# stoplight.net
KiCad netlist of a schematic drawn in EAGLE
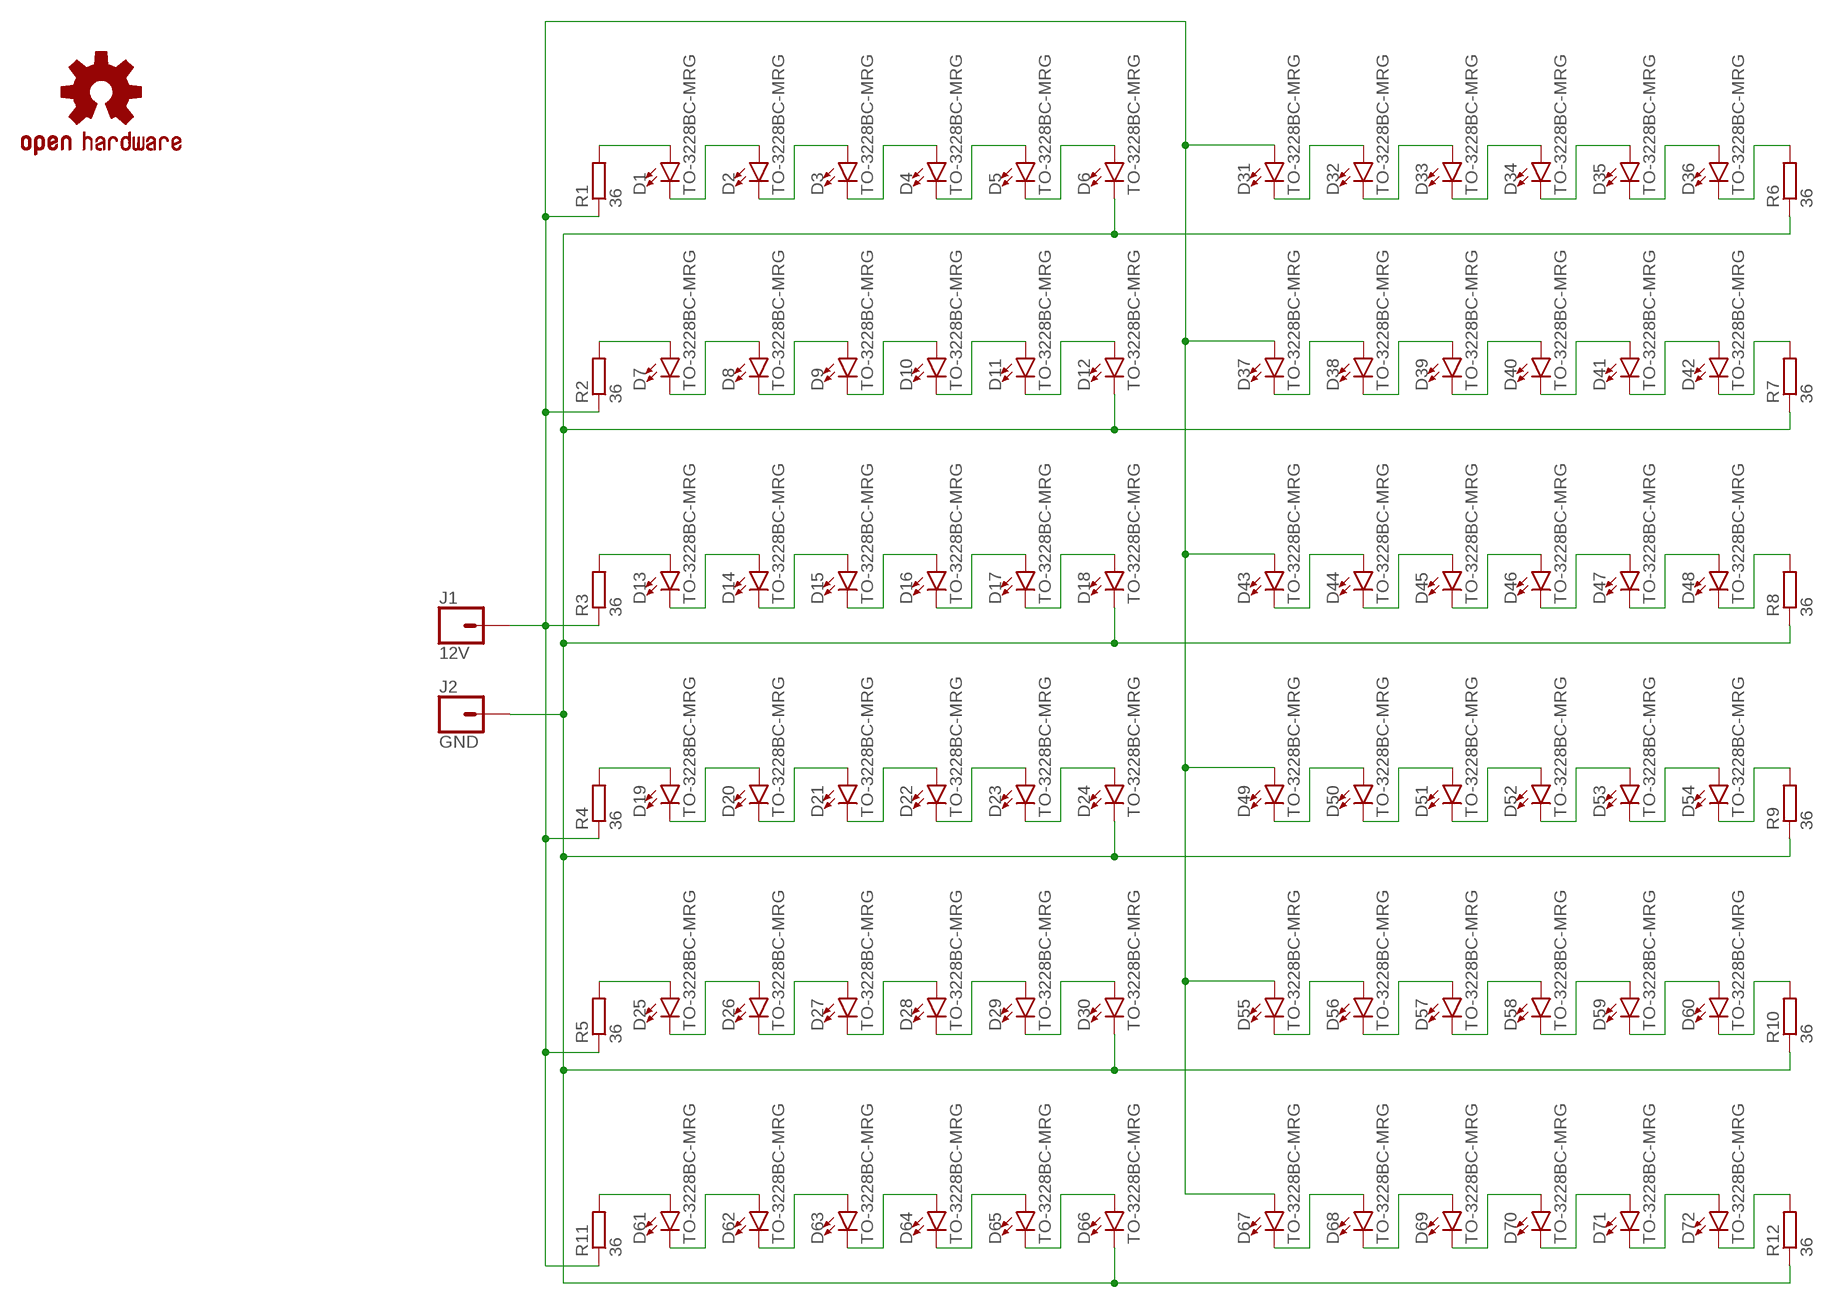
[diagram p0: schematic, sheet 1]

(export (version "E")
  (design (tool "Eeschema 10.0.6"))
  (components
    (comp (ref "D1")
      (value "TO-3228BC-MRG")
      (footprint "eagle-import:TO-3228BC")
      (libsource (lib "eagle-import") (part "TO-3228BC-MRG"))
    )
    (comp (ref "D2")
      (value "TO-3228BC-MRG")
      (footprint "eagle-import:TO-3228BC")
      (libsource (lib "eagle-import") (part "TO-3228BC-MRG"))
    )
    (comp (ref "D3")
      (value "TO-3228BC-MRG")
      (footprint "eagle-import:TO-3228BC")
      (libsource (lib "eagle-import") (part "TO-3228BC-MRG"))
    )
    (comp (ref "D4")
      (value "TO-3228BC-MRG")
      (footprint "eagle-import:TO-3228BC")
      (libsource (lib "eagle-import") (part "TO-3228BC-MRG"))
    )
    (comp (ref "D5")
      (value "TO-3228BC-MRG")
      (footprint "eagle-import:TO-3228BC")
      (libsource (lib "eagle-import") (part "TO-3228BC-MRG"))
    )
    (comp (ref "D6")
      (value "TO-3228BC-MRG")
      (footprint "eagle-import:TO-3228BC")
      (libsource (lib "eagle-import") (part "TO-3228BC-MRG"))
    )
    (comp (ref "D7")
      (value "TO-3228BC-MRG")
      (footprint "eagle-import:TO-3228BC")
      (libsource (lib "eagle-import") (part "TO-3228BC-MRG"))
    )
    (comp (ref "D8")
      (value "TO-3228BC-MRG")
      (footprint "eagle-import:TO-3228BC")
      (libsource (lib "eagle-import") (part "TO-3228BC-MRG"))
    )
    (comp (ref "D9")
      (value "TO-3228BC-MRG")
      (footprint "eagle-import:TO-3228BC")
      (libsource (lib "eagle-import") (part "TO-3228BC-MRG"))
    )
    (comp (ref "D10")
      (value "TO-3228BC-MRG")
      (footprint "eagle-import:TO-3228BC")
      (libsource (lib "eagle-import") (part "TO-3228BC-MRG"))
    )
    (comp (ref "D11")
      (value "TO-3228BC-MRG")
      (footprint "eagle-import:TO-3228BC")
      (libsource (lib "eagle-import") (part "TO-3228BC-MRG"))
    )
    (comp (ref "D12")
      (value "TO-3228BC-MRG")
      (footprint "eagle-import:TO-3228BC")
      (libsource (lib "eagle-import") (part "TO-3228BC-MRG"))
    )
    (comp (ref "D13")
      (value "TO-3228BC-MRG")
      (footprint "eagle-import:TO-3228BC")
      (libsource (lib "eagle-import") (part "TO-3228BC-MRG"))
    )
    (comp (ref "D14")
      (value "TO-3228BC-MRG")
      (footprint "eagle-import:TO-3228BC")
      (libsource (lib "eagle-import") (part "TO-3228BC-MRG"))
    )
    (comp (ref "D15")
      (value "TO-3228BC-MRG")
      (footprint "eagle-import:TO-3228BC")
      (libsource (lib "eagle-import") (part "TO-3228BC-MRG"))
    )
    (comp (ref "D16")
      (value "TO-3228BC-MRG")
      (footprint "eagle-import:TO-3228BC")
      (libsource (lib "eagle-import") (part "TO-3228BC-MRG"))
    )
    (comp (ref "D17")
      (value "TO-3228BC-MRG")
      (footprint "eagle-import:TO-3228BC")
      (libsource (lib "eagle-import") (part "TO-3228BC-MRG"))
    )
    (comp (ref "D18")
      (value "TO-3228BC-MRG")
      (footprint "eagle-import:TO-3228BC")
      (libsource (lib "eagle-import") (part "TO-3228BC-MRG"))
    )
    (comp (ref "D19")
      (value "TO-3228BC-MRG")
      (footprint "eagle-import:TO-3228BC")
      (libsource (lib "eagle-import") (part "TO-3228BC-MRG"))
    )
    (comp (ref "D20")
      (value "TO-3228BC-MRG")
      (footprint "eagle-import:TO-3228BC")
      (libsource (lib "eagle-import") (part "TO-3228BC-MRG"))
    )
    (comp (ref "D21")
      (value "TO-3228BC-MRG")
      (footprint "eagle-import:TO-3228BC")
      (libsource (lib "eagle-import") (part "TO-3228BC-MRG"))
    )
    (comp (ref "D22")
      (value "TO-3228BC-MRG")
      (footprint "eagle-import:TO-3228BC")
      (libsource (lib "eagle-import") (part "TO-3228BC-MRG"))
    )
    (comp (ref "D23")
      (value "TO-3228BC-MRG")
      (footprint "eagle-import:TO-3228BC")
      (libsource (lib "eagle-import") (part "TO-3228BC-MRG"))
    )
    (comp (ref "D24")
      (value "TO-3228BC-MRG")
      (footprint "eagle-import:TO-3228BC")
      (libsource (lib "eagle-import") (part "TO-3228BC-MRG"))
    )
    (comp (ref "D25")
      (value "TO-3228BC-MRG")
      (footprint "eagle-import:TO-3228BC")
      (libsource (lib "eagle-import") (part "TO-3228BC-MRG"))
    )
    (comp (ref "D26")
      (value "TO-3228BC-MRG")
      (footprint "eagle-import:TO-3228BC")
      (libsource (lib "eagle-import") (part "TO-3228BC-MRG"))
    )
    (comp (ref "D27")
      (value "TO-3228BC-MRG")
      (footprint "eagle-import:TO-3228BC")
      (libsource (lib "eagle-import") (part "TO-3228BC-MRG"))
    )
    (comp (ref "D28")
      (value "TO-3228BC-MRG")
      (footprint "eagle-import:TO-3228BC")
      (libsource (lib "eagle-import") (part "TO-3228BC-MRG"))
    )
    (comp (ref "D29")
      (value "TO-3228BC-MRG")
      (footprint "eagle-import:TO-3228BC")
      (libsource (lib "eagle-import") (part "TO-3228BC-MRG"))
    )
    (comp (ref "D30")
      (value "TO-3228BC-MRG")
      (footprint "eagle-import:TO-3228BC")
      (libsource (lib "eagle-import") (part "TO-3228BC-MRG"))
    )
    (comp (ref "D31")
      (value "TO-3228BC-MRG")
      (footprint "eagle-import:TO-3228BC")
      (libsource (lib "eagle-import") (part "TO-3228BC-MRG"))
    )
    (comp (ref "D32")
      (value "TO-3228BC-MRG")
      (footprint "eagle-import:TO-3228BC")
      (libsource (lib "eagle-import") (part "TO-3228BC-MRG"))
    )
    (comp (ref "D33")
      (value "TO-3228BC-MRG")
      (footprint "eagle-import:TO-3228BC")
      (libsource (lib "eagle-import") (part "TO-3228BC-MRG"))
    )
    (comp (ref "D34")
      (value "TO-3228BC-MRG")
      (footprint "eagle-import:TO-3228BC")
      (libsource (lib "eagle-import") (part "TO-3228BC-MRG"))
    )
    (comp (ref "D35")
      (value "TO-3228BC-MRG")
      (footprint "eagle-import:TO-3228BC")
      (libsource (lib "eagle-import") (part "TO-3228BC-MRG"))
    )
    (comp (ref "D36")
      (value "TO-3228BC-MRG")
      (footprint "eagle-import:TO-3228BC")
      (libsource (lib "eagle-import") (part "TO-3228BC-MRG"))
    )
    (comp (ref "D37")
      (value "TO-3228BC-MRG")
      (footprint "eagle-import:TO-3228BC")
      (libsource (lib "eagle-import") (part "TO-3228BC-MRG"))
    )
    (comp (ref "D38")
      (value "TO-3228BC-MRG")
      (footprint "eagle-import:TO-3228BC")
      (libsource (lib "eagle-import") (part "TO-3228BC-MRG"))
    )
    (comp (ref "D39")
      (value "TO-3228BC-MRG")
      (footprint "eagle-import:TO-3228BC")
      (libsource (lib "eagle-import") (part "TO-3228BC-MRG"))
    )
    (comp (ref "D40")
      (value "TO-3228BC-MRG")
      (footprint "eagle-import:TO-3228BC")
      (libsource (lib "eagle-import") (part "TO-3228BC-MRG"))
    )
    (comp (ref "D41")
      (value "TO-3228BC-MRG")
      (footprint "eagle-import:TO-3228BC")
      (libsource (lib "eagle-import") (part "TO-3228BC-MRG"))
    )
    (comp (ref "D42")
      (value "TO-3228BC-MRG")
      (footprint "eagle-import:TO-3228BC")
      (libsource (lib "eagle-import") (part "TO-3228BC-MRG"))
    )
    (comp (ref "D43")
      (value "TO-3228BC-MRG")
      (footprint "eagle-import:TO-3228BC")
      (libsource (lib "eagle-import") (part "TO-3228BC-MRG"))
    )
    (comp (ref "D44")
      (value "TO-3228BC-MRG")
      (footprint "eagle-import:TO-3228BC")
      (libsource (lib "eagle-import") (part "TO-3228BC-MRG"))
    )
    (comp (ref "D45")
      (value "TO-3228BC-MRG")
      (footprint "eagle-import:TO-3228BC")
      (libsource (lib "eagle-import") (part "TO-3228BC-MRG"))
    )
    (comp (ref "D46")
      (value "TO-3228BC-MRG")
      (footprint "eagle-import:TO-3228BC")
      (libsource (lib "eagle-import") (part "TO-3228BC-MRG"))
    )
    (comp (ref "D47")
      (value "TO-3228BC-MRG")
      (footprint "eagle-import:TO-3228BC")
      (libsource (lib "eagle-import") (part "TO-3228BC-MRG"))
    )
    (comp (ref "D48")
      (value "TO-3228BC-MRG")
      (footprint "eagle-import:TO-3228BC")
      (libsource (lib "eagle-import") (part "TO-3228BC-MRG"))
    )
    (comp (ref "D49")
      (value "TO-3228BC-MRG")
      (footprint "eagle-import:TO-3228BC")
      (libsource (lib "eagle-import") (part "TO-3228BC-MRG"))
    )
    (comp (ref "D50")
      (value "TO-3228BC-MRG")
      (footprint "eagle-import:TO-3228BC")
      (libsource (lib "eagle-import") (part "TO-3228BC-MRG"))
    )
    (comp (ref "D51")
      (value "TO-3228BC-MRG")
      (footprint "eagle-import:TO-3228BC")
      (libsource (lib "eagle-import") (part "TO-3228BC-MRG"))
    )
    (comp (ref "D52")
      (value "TO-3228BC-MRG")
      (footprint "eagle-import:TO-3228BC")
      (libsource (lib "eagle-import") (part "TO-3228BC-MRG"))
    )
    (comp (ref "D53")
      (value "TO-3228BC-MRG")
      (footprint "eagle-import:TO-3228BC")
      (libsource (lib "eagle-import") (part "TO-3228BC-MRG"))
    )
    (comp (ref "D54")
      (value "TO-3228BC-MRG")
      (footprint "eagle-import:TO-3228BC")
      (libsource (lib "eagle-import") (part "TO-3228BC-MRG"))
    )
    (comp (ref "D55")
      (value "TO-3228BC-MRG")
      (footprint "eagle-import:TO-3228BC")
      (libsource (lib "eagle-import") (part "TO-3228BC-MRG"))
    )
    (comp (ref "D56")
      (value "TO-3228BC-MRG")
      (footprint "eagle-import:TO-3228BC")
      (libsource (lib "eagle-import") (part "TO-3228BC-MRG"))
    )
    (comp (ref "D57")
      (value "TO-3228BC-MRG")
      (footprint "eagle-import:TO-3228BC")
      (libsource (lib "eagle-import") (part "TO-3228BC-MRG"))
    )
    (comp (ref "D58")
      (value "TO-3228BC-MRG")
      (footprint "eagle-import:TO-3228BC")
      (libsource (lib "eagle-import") (part "TO-3228BC-MRG"))
    )
    (comp (ref "D59")
      (value "TO-3228BC-MRG")
      (footprint "eagle-import:TO-3228BC")
      (libsource (lib "eagle-import") (part "TO-3228BC-MRG"))
    )
    (comp (ref "D60")
      (value "TO-3228BC-MRG")
      (footprint "eagle-import:TO-3228BC")
      (libsource (lib "eagle-import") (part "TO-3228BC-MRG"))
    )
    (comp (ref "D61")
      (value "TO-3228BC-MRG")
      (footprint "eagle-import:TO-3228BC")
      (libsource (lib "eagle-import") (part "TO-3228BC-MRG"))
    )
    (comp (ref "D62")
      (value "TO-3228BC-MRG")
      (footprint "eagle-import:TO-3228BC")
      (libsource (lib "eagle-import") (part "TO-3228BC-MRG"))
    )
    (comp (ref "D63")
      (value "TO-3228BC-MRG")
      (footprint "eagle-import:TO-3228BC")
      (libsource (lib "eagle-import") (part "TO-3228BC-MRG"))
    )
    (comp (ref "D64")
      (value "TO-3228BC-MRG")
      (footprint "eagle-import:TO-3228BC")
      (libsource (lib "eagle-import") (part "TO-3228BC-MRG"))
    )
    (comp (ref "D65")
      (value "TO-3228BC-MRG")
      (footprint "eagle-import:TO-3228BC")
      (libsource (lib "eagle-import") (part "TO-3228BC-MRG"))
    )
    (comp (ref "D66")
      (value "TO-3228BC-MRG")
      (footprint "eagle-import:TO-3228BC")
      (libsource (lib "eagle-import") (part "TO-3228BC-MRG"))
    )
    (comp (ref "D67")
      (value "TO-3228BC-MRG")
      (footprint "eagle-import:TO-3228BC")
      (libsource (lib "eagle-import") (part "TO-3228BC-MRG"))
    )
    (comp (ref "D68")
      (value "TO-3228BC-MRG")
      (footprint "eagle-import:TO-3228BC")
      (libsource (lib "eagle-import") (part "TO-3228BC-MRG"))
    )
    (comp (ref "D69")
      (value "TO-3228BC-MRG")
      (footprint "eagle-import:TO-3228BC")
      (libsource (lib "eagle-import") (part "TO-3228BC-MRG"))
    )
    (comp (ref "D70")
      (value "TO-3228BC-MRG")
      (footprint "eagle-import:TO-3228BC")
      (libsource (lib "eagle-import") (part "TO-3228BC-MRG"))
    )
    (comp (ref "D71")
      (value "TO-3228BC-MRG")
      (footprint "eagle-import:TO-3228BC")
      (libsource (lib "eagle-import") (part "TO-3228BC-MRG"))
    )
    (comp (ref "D72")
      (value "TO-3228BC-MRG")
      (footprint "eagle-import:TO-3228BC")
      (libsource (lib "eagle-import") (part "TO-3228BC-MRG"))
    )
    (comp (ref "J1")
      (value "12V")
      (footprint "eagle-import:1X01_LONGPAD")
      (libsource (lib "eagle-import") (part "CONN_01PTH_LONGPAD"))
    )
    (comp (ref "J2")
      (value "GND")
      (footprint "eagle-import:1X01_LONGPAD")
      (libsource (lib "eagle-import") (part "CONN_01PTH_LONGPAD"))
    )
    (comp (ref "LOGO1")
      (value "OSHW-LOGOS-COPPER")
      (footprint "eagle-import:OSHW-LOGO-S_COPPER")
      (libsource (lib "eagle-import") (part "OSHW-LOGOS-COPPER"))
    )
    (comp (ref "R1")
      (value "36")
      (footprint "eagle-import:R0805")
      (libsource (lib "eagle-import") (part "R-EU_R0805"))
    )
    (comp (ref "R2")
      (value "36")
      (footprint "eagle-import:R0805")
      (libsource (lib "eagle-import") (part "R-EU_R0805"))
    )
    (comp (ref "R3")
      (value "36")
      (footprint "eagle-import:R0805")
      (libsource (lib "eagle-import") (part "R-EU_R0805"))
    )
    (comp (ref "R4")
      (value "36")
      (footprint "eagle-import:R0805")
      (libsource (lib "eagle-import") (part "R-EU_R0805"))
    )
    (comp (ref "R5")
      (value "36")
      (footprint "eagle-import:R0805")
      (libsource (lib "eagle-import") (part "R-EU_R0805"))
    )
    (comp (ref "R6")
      (value "36")
      (footprint "eagle-import:R0805")
      (libsource (lib "eagle-import") (part "R-EU_R0805"))
    )
    (comp (ref "R7")
      (value "36")
      (footprint "eagle-import:R0805")
      (libsource (lib "eagle-import") (part "R-EU_R0805"))
    )
    (comp (ref "R8")
      (value "36")
      (footprint "eagle-import:R0805")
      (libsource (lib "eagle-import") (part "R-EU_R0805"))
    )
    (comp (ref "R9")
      (value "36")
      (footprint "eagle-import:R0805")
      (libsource (lib "eagle-import") (part "R-EU_R0805"))
    )
    (comp (ref "R10")
      (value "36")
      (footprint "eagle-import:R0805")
      (libsource (lib "eagle-import") (part "R-EU_R0805"))
    )
    (comp (ref "R11")
      (value "36")
      (footprint "eagle-import:R0805")
      (libsource (lib "eagle-import") (part "R-EU_R0805"))
    )
    (comp (ref "R12")
      (value "36")
      (footprint "eagle-import:R0805")
      (libsource (lib "eagle-import") (part "R-EU_R0805"))
    )
  )
  (nets
    (net (code "1") (name "Net-(D1-PadA)") (class "Default")
      (node (ref "D1") (pin "A") (pinfunction "A_A") (pintype "passive"))
      (node (ref "R1") (pin "2") (pinfunction "2_2") (pintype "passive"))
    )
    (net (code "2") (name "Net-(D1-PadC)") (class "Default")
      (node (ref "D1") (pin "C") (pinfunction "C_C") (pintype "passive"))
      (node (ref "D2") (pin "A") (pinfunction "A_A") (pintype "passive"))
    )
    (net (code "3") (name "Net-(D2-PadC)") (class "Default")
      (node (ref "D2") (pin "C") (pinfunction "C_C") (pintype "passive"))
      (node (ref "D3") (pin "A") (pinfunction "A_A") (pintype "passive"))
    )
    (net (code "4") (name "Net-(D3-PadC)") (class "Default")
      (node (ref "D3") (pin "C") (pinfunction "C_C") (pintype "passive"))
      (node (ref "D4") (pin "A") (pinfunction "A_A") (pintype "passive"))
    )
    (net (code "5") (name "Net-(D4-PadC)") (class "Default")
      (node (ref "D4") (pin "C") (pinfunction "C_C") (pintype "passive"))
      (node (ref "D5") (pin "A") (pinfunction "A_A") (pintype "passive"))
    )
    (net (code "6") (name "Net-(D5-PadC)") (class "Default")
      (node (ref "D5") (pin "C") (pinfunction "C_C") (pintype "passive"))
      (node (ref "D6") (pin "A") (pinfunction "A_A") (pintype "passive"))
    )
    (net (code "7") (name "Net-(D7-PadA)") (class "Default")
      (node (ref "D7") (pin "A") (pinfunction "A_A") (pintype "passive"))
      (node (ref "R2") (pin "2") (pinfunction "2_2") (pintype "passive"))
    )
    (net (code "8") (name "Net-(D7-PadC)") (class "Default")
      (node (ref "D7") (pin "C") (pinfunction "C_C") (pintype "passive"))
      (node (ref "D8") (pin "A") (pinfunction "A_A") (pintype "passive"))
    )
    (net (code "9") (name "Net-(D8-PadC)") (class "Default")
      (node (ref "D8") (pin "C") (pinfunction "C_C") (pintype "passive"))
      (node (ref "D9") (pin "A") (pinfunction "A_A") (pintype "passive"))
    )
    (net (code "10") (name "Net-(D10-PadA)") (class "Default")
      (node (ref "D10") (pin "A") (pinfunction "A_A") (pintype "passive"))
      (node (ref "D9") (pin "C") (pinfunction "C_C") (pintype "passive"))
    )
    (net (code "11") (name "Net-(D10-PadC)") (class "Default")
      (node (ref "D10") (pin "C") (pinfunction "C_C") (pintype "passive"))
      (node (ref "D11") (pin "A") (pinfunction "A_A") (pintype "passive"))
    )
    (net (code "12") (name "Net-(D11-PadC)") (class "Default")
      (node (ref "D11") (pin "C") (pinfunction "C_C") (pintype "passive"))
      (node (ref "D12") (pin "A") (pinfunction "A_A") (pintype "passive"))
    )
    (net (code "13") (name "Net-(D12-PadC)") (class "Default")
      (node (ref "D12") (pin "C") (pinfunction "C_C") (pintype "passive"))
      (node (ref "D18") (pin "C") (pinfunction "C_C") (pintype "passive"))
      (node (ref "D24") (pin "C") (pinfunction "C_C") (pintype "passive"))
      (node (ref "D30") (pin "C") (pinfunction "C_C") (pintype "passive"))
      (node (ref "D6") (pin "C") (pinfunction "C_C") (pintype "passive"))
      (node (ref "D66") (pin "C") (pinfunction "C_C") (pintype "passive"))
      (node (ref "J2") (pin "1") (pinfunction "1_1") (pintype "passive"))
      (node (ref "R10") (pin "1") (pinfunction "1_1") (pintype "passive"))
      (node (ref "R12") (pin "1") (pinfunction "1_1") (pintype "passive"))
      (node (ref "R6") (pin "1") (pinfunction "1_1") (pintype "passive"))
      (node (ref "R7") (pin "1") (pinfunction "1_1") (pintype "passive"))
      (node (ref "R8") (pin "1") (pinfunction "1_1") (pintype "passive"))
      (node (ref "R9") (pin "1") (pinfunction "1_1") (pintype "passive"))
    )
    (net (code "14") (name "Net-(D13-PadA)") (class "Default")
      (node (ref "D13") (pin "A") (pinfunction "A_A") (pintype "passive"))
      (node (ref "R3") (pin "2") (pinfunction "2_2") (pintype "passive"))
    )
    (net (code "15") (name "Net-(D13-PadC)") (class "Default")
      (node (ref "D13") (pin "C") (pinfunction "C_C") (pintype "passive"))
      (node (ref "D14") (pin "A") (pinfunction "A_A") (pintype "passive"))
    )
    (net (code "16") (name "Net-(D14-PadC)") (class "Default")
      (node (ref "D14") (pin "C") (pinfunction "C_C") (pintype "passive"))
      (node (ref "D15") (pin "A") (pinfunction "A_A") (pintype "passive"))
    )
    (net (code "17") (name "Net-(D15-PadC)") (class "Default")
      (node (ref "D15") (pin "C") (pinfunction "C_C") (pintype "passive"))
      (node (ref "D16") (pin "A") (pinfunction "A_A") (pintype "passive"))
    )
    (net (code "18") (name "Net-(D16-PadC)") (class "Default")
      (node (ref "D16") (pin "C") (pinfunction "C_C") (pintype "passive"))
      (node (ref "D17") (pin "A") (pinfunction "A_A") (pintype "passive"))
    )
    (net (code "19") (name "Net-(D17-PadC)") (class "Default")
      (node (ref "D17") (pin "C") (pinfunction "C_C") (pintype "passive"))
      (node (ref "D18") (pin "A") (pinfunction "A_A") (pintype "passive"))
    )
    (net (code "20") (name "Net-(D19-PadA)") (class "Default")
      (node (ref "D19") (pin "A") (pinfunction "A_A") (pintype "passive"))
      (node (ref "R4") (pin "2") (pinfunction "2_2") (pintype "passive"))
    )
    (net (code "21") (name "Net-(D19-PadC)") (class "Default")
      (node (ref "D19") (pin "C") (pinfunction "C_C") (pintype "passive"))
      (node (ref "D20") (pin "A") (pinfunction "A_A") (pintype "passive"))
    )
    (net (code "22") (name "Net-(D20-PadC)") (class "Default")
      (node (ref "D20") (pin "C") (pinfunction "C_C") (pintype "passive"))
      (node (ref "D21") (pin "A") (pinfunction "A_A") (pintype "passive"))
    )
    (net (code "23") (name "Net-(D21-PadC)") (class "Default")
      (node (ref "D21") (pin "C") (pinfunction "C_C") (pintype "passive"))
      (node (ref "D22") (pin "A") (pinfunction "A_A") (pintype "passive"))
    )
    (net (code "24") (name "Net-(D22-PadC)") (class "Default")
      (node (ref "D22") (pin "C") (pinfunction "C_C") (pintype "passive"))
      (node (ref "D23") (pin "A") (pinfunction "A_A") (pintype "passive"))
    )
    (net (code "25") (name "Net-(D23-PadC)") (class "Default")
      (node (ref "D23") (pin "C") (pinfunction "C_C") (pintype "passive"))
      (node (ref "D24") (pin "A") (pinfunction "A_A") (pintype "passive"))
    )
    (net (code "26") (name "Net-(D25-PadA)") (class "Default")
      (node (ref "D25") (pin "A") (pinfunction "A_A") (pintype "passive"))
      (node (ref "R5") (pin "2") (pinfunction "2_2") (pintype "passive"))
    )
    (net (code "27") (name "Net-(D25-PadC)") (class "Default")
      (node (ref "D25") (pin "C") (pinfunction "C_C") (pintype "passive"))
      (node (ref "D26") (pin "A") (pinfunction "A_A") (pintype "passive"))
    )
    (net (code "28") (name "Net-(D26-PadC)") (class "Default")
      (node (ref "D26") (pin "C") (pinfunction "C_C") (pintype "passive"))
      (node (ref "D27") (pin "A") (pinfunction "A_A") (pintype "passive"))
    )
    (net (code "29") (name "Net-(D27-PadC)") (class "Default")
      (node (ref "D27") (pin "C") (pinfunction "C_C") (pintype "passive"))
      (node (ref "D28") (pin "A") (pinfunction "A_A") (pintype "passive"))
    )
    (net (code "30") (name "Net-(D28-PadC)") (class "Default")
      (node (ref "D28") (pin "C") (pinfunction "C_C") (pintype "passive"))
      (node (ref "D29") (pin "A") (pinfunction "A_A") (pintype "passive"))
    )
    (net (code "31") (name "Net-(D29-PadC)") (class "Default")
      (node (ref "D29") (pin "C") (pinfunction "C_C") (pintype "passive"))
      (node (ref "D30") (pin "A") (pinfunction "A_A") (pintype "passive"))
    )
    (net (code "32") (name "Net-(D31-PadA)") (class "Default")
      (node (ref "D31") (pin "A") (pinfunction "A_A") (pintype "passive"))
      (node (ref "D37") (pin "A") (pinfunction "A_A") (pintype "passive"))
      (node (ref "D43") (pin "A") (pinfunction "A_A") (pintype "passive"))
      (node (ref "D49") (pin "A") (pinfunction "A_A") (pintype "passive"))
      (node (ref "D55") (pin "A") (pinfunction "A_A") (pintype "passive"))
      (node (ref "D67") (pin "A") (pinfunction "A_A") (pintype "passive"))
      (node (ref "J1") (pin "1") (pinfunction "1_1") (pintype "passive"))
      (node (ref "R1") (pin "1") (pinfunction "1_1") (pintype "passive"))
      (node (ref "R11") (pin "1") (pinfunction "1_1") (pintype "passive"))
      (node (ref "R2") (pin "1") (pinfunction "1_1") (pintype "passive"))
      (node (ref "R3") (pin "1") (pinfunction "1_1") (pintype "passive"))
      (node (ref "R4") (pin "1") (pinfunction "1_1") (pintype "passive"))
      (node (ref "R5") (pin "1") (pinfunction "1_1") (pintype "passive"))
    )
    (net (code "33") (name "Net-(D31-PadC)") (class "Default")
      (node (ref "D31") (pin "C") (pinfunction "C_C") (pintype "passive"))
      (node (ref "D32") (pin "A") (pinfunction "A_A") (pintype "passive"))
    )
    (net (code "34") (name "Net-(D32-PadC)") (class "Default")
      (node (ref "D32") (pin "C") (pinfunction "C_C") (pintype "passive"))
      (node (ref "D33") (pin "A") (pinfunction "A_A") (pintype "passive"))
    )
    (net (code "35") (name "Net-(D33-PadC)") (class "Default")
      (node (ref "D33") (pin "C") (pinfunction "C_C") (pintype "passive"))
      (node (ref "D34") (pin "A") (pinfunction "A_A") (pintype "passive"))
    )
    (net (code "36") (name "Net-(D34-PadC)") (class "Default")
      (node (ref "D34") (pin "C") (pinfunction "C_C") (pintype "passive"))
      (node (ref "D35") (pin "A") (pinfunction "A_A") (pintype "passive"))
    )
    (net (code "37") (name "Net-(D35-PadC)") (class "Default")
      (node (ref "D35") (pin "C") (pinfunction "C_C") (pintype "passive"))
      (node (ref "D36") (pin "A") (pinfunction "A_A") (pintype "passive"))
    )
    (net (code "38") (name "Net-(D36-PadC)") (class "Default")
      (node (ref "D36") (pin "C") (pinfunction "C_C") (pintype "passive"))
      (node (ref "R6") (pin "2") (pinfunction "2_2") (pintype "passive"))
    )
    (net (code "39") (name "Net-(D37-PadC)") (class "Default")
      (node (ref "D37") (pin "C") (pinfunction "C_C") (pintype "passive"))
      (node (ref "D38") (pin "A") (pinfunction "A_A") (pintype "passive"))
    )
    (net (code "40") (name "Net-(D38-PadC)") (class "Default")
      (node (ref "D38") (pin "C") (pinfunction "C_C") (pintype "passive"))
      (node (ref "D39") (pin "A") (pinfunction "A_A") (pintype "passive"))
    )
    (net (code "41") (name "Net-(D39-PadC)") (class "Default")
      (node (ref "D39") (pin "C") (pinfunction "C_C") (pintype "passive"))
      (node (ref "D40") (pin "A") (pinfunction "A_A") (pintype "passive"))
    )
    (net (code "42") (name "Net-(D40-PadC)") (class "Default")
      (node (ref "D40") (pin "C") (pinfunction "C_C") (pintype "passive"))
      (node (ref "D41") (pin "A") (pinfunction "A_A") (pintype "passive"))
    )
    (net (code "43") (name "Net-(D41-PadC)") (class "Default")
      (node (ref "D41") (pin "C") (pinfunction "C_C") (pintype "passive"))
      (node (ref "D42") (pin "A") (pinfunction "A_A") (pintype "passive"))
    )
    (net (code "44") (name "Net-(D42-PadC)") (class "Default")
      (node (ref "D42") (pin "C") (pinfunction "C_C") (pintype "passive"))
      (node (ref "R7") (pin "2") (pinfunction "2_2") (pintype "passive"))
    )
    (net (code "45") (name "Net-(D43-PadC)") (class "Default")
      (node (ref "D43") (pin "C") (pinfunction "C_C") (pintype "passive"))
      (node (ref "D44") (pin "A") (pinfunction "A_A") (pintype "passive"))
    )
    (net (code "46") (name "Net-(D44-PadC)") (class "Default")
      (node (ref "D44") (pin "C") (pinfunction "C_C") (pintype "passive"))
      (node (ref "D45") (pin "A") (pinfunction "A_A") (pintype "passive"))
    )
    (net (code "47") (name "Net-(D45-PadC)") (class "Default")
      (node (ref "D45") (pin "C") (pinfunction "C_C") (pintype "passive"))
      (node (ref "D46") (pin "A") (pinfunction "A_A") (pintype "passive"))
    )
    (net (code "48") (name "Net-(D46-PadC)") (class "Default")
      (node (ref "D46") (pin "C") (pinfunction "C_C") (pintype "passive"))
      (node (ref "D47") (pin "A") (pinfunction "A_A") (pintype "passive"))
    )
    (net (code "49") (name "Net-(D47-PadC)") (class "Default")
      (node (ref "D47") (pin "C") (pinfunction "C_C") (pintype "passive"))
      (node (ref "D48") (pin "A") (pinfunction "A_A") (pintype "passive"))
    )
    (net (code "50") (name "Net-(D48-PadC)") (class "Default")
      (node (ref "D48") (pin "C") (pinfunction "C_C") (pintype "passive"))
      (node (ref "R8") (pin "2") (pinfunction "2_2") (pintype "passive"))
    )
    (net (code "51") (name "Net-(D49-PadC)") (class "Default")
      (node (ref "D49") (pin "C") (pinfunction "C_C") (pintype "passive"))
      (node (ref "D50") (pin "A") (pinfunction "A_A") (pintype "passive"))
    )
    (net (code "52") (name "Net-(D50-PadC)") (class "Default")
      (node (ref "D50") (pin "C") (pinfunction "C_C") (pintype "passive"))
      (node (ref "D51") (pin "A") (pinfunction "A_A") (pintype "passive"))
    )
    (net (code "53") (name "Net-(D51-PadC)") (class "Default")
      (node (ref "D51") (pin "C") (pinfunction "C_C") (pintype "passive"))
      (node (ref "D52") (pin "A") (pinfunction "A_A") (pintype "passive"))
    )
    (net (code "54") (name "Net-(D52-PadC)") (class "Default")
      (node (ref "D52") (pin "C") (pinfunction "C_C") (pintype "passive"))
      (node (ref "D53") (pin "A") (pinfunction "A_A") (pintype "passive"))
    )
    (net (code "55") (name "Net-(D53-PadC)") (class "Default")
      (node (ref "D53") (pin "C") (pinfunction "C_C") (pintype "passive"))
      (node (ref "D54") (pin "A") (pinfunction "A_A") (pintype "passive"))
    )
    (net (code "56") (name "Net-(D54-PadC)") (class "Default")
      (node (ref "D54") (pin "C") (pinfunction "C_C") (pintype "passive"))
      (node (ref "R9") (pin "2") (pinfunction "2_2") (pintype "passive"))
    )
    (net (code "57") (name "Net-(D55-PadC)") (class "Default")
      (node (ref "D55") (pin "C") (pinfunction "C_C") (pintype "passive"))
      (node (ref "D56") (pin "A") (pinfunction "A_A") (pintype "passive"))
    )
    (net (code "58") (name "Net-(D56-PadC)") (class "Default")
      (node (ref "D56") (pin "C") (pinfunction "C_C") (pintype "passive"))
      (node (ref "D57") (pin "A") (pinfunction "A_A") (pintype "passive"))
    )
    (net (code "59") (name "Net-(D57-PadC)") (class "Default")
      (node (ref "D57") (pin "C") (pinfunction "C_C") (pintype "passive"))
      (node (ref "D58") (pin "A") (pinfunction "A_A") (pintype "passive"))
    )
    (net (code "60") (name "Net-(D58-PadC)") (class "Default")
      (node (ref "D58") (pin "C") (pinfunction "C_C") (pintype "passive"))
      (node (ref "D59") (pin "A") (pinfunction "A_A") (pintype "passive"))
    )
    (net (code "61") (name "Net-(D59-PadC)") (class "Default")
      (node (ref "D59") (pin "C") (pinfunction "C_C") (pintype "passive"))
      (node (ref "D60") (pin "A") (pinfunction "A_A") (pintype "passive"))
    )
    (net (code "62") (name "Net-(D60-PadC)") (class "Default")
      (node (ref "D60") (pin "C") (pinfunction "C_C") (pintype "passive"))
      (node (ref "R10") (pin "2") (pinfunction "2_2") (pintype "passive"))
    )
    (net (code "63") (name "Net-(D61-PadA)") (class "Default")
      (node (ref "D61") (pin "A") (pinfunction "A_A") (pintype "passive"))
      (node (ref "R11") (pin "2") (pinfunction "2_2") (pintype "passive"))
    )
    (net (code "64") (name "Net-(D61-PadC)") (class "Default")
      (node (ref "D61") (pin "C") (pinfunction "C_C") (pintype "passive"))
      (node (ref "D62") (pin "A") (pinfunction "A_A") (pintype "passive"))
    )
    (net (code "65") (name "Net-(D62-PadC)") (class "Default")
      (node (ref "D62") (pin "C") (pinfunction "C_C") (pintype "passive"))
      (node (ref "D63") (pin "A") (pinfunction "A_A") (pintype "passive"))
    )
    (net (code "66") (name "Net-(D63-PadC)") (class "Default")
      (node (ref "D63") (pin "C") (pinfunction "C_C") (pintype "passive"))
      (node (ref "D64") (pin "A") (pinfunction "A_A") (pintype "passive"))
    )
    (net (code "67") (name "Net-(D64-PadC)") (class "Default")
      (node (ref "D64") (pin "C") (pinfunction "C_C") (pintype "passive"))
      (node (ref "D65") (pin "A") (pinfunction "A_A") (pintype "passive"))
    )
    (net (code "68") (name "Net-(D65-PadC)") (class "Default")
      (node (ref "D65") (pin "C") (pinfunction "C_C") (pintype "passive"))
      (node (ref "D66") (pin "A") (pinfunction "A_A") (pintype "passive"))
    )
    (net (code "69") (name "Net-(D67-PadC)") (class "Default")
      (node (ref "D67") (pin "C") (pinfunction "C_C") (pintype "passive"))
      (node (ref "D68") (pin "A") (pinfunction "A_A") (pintype "passive"))
    )
    (net (code "70") (name "Net-(D68-PadC)") (class "Default")
      (node (ref "D68") (pin "C") (pinfunction "C_C") (pintype "passive"))
      (node (ref "D69") (pin "A") (pinfunction "A_A") (pintype "passive"))
    )
    (net (code "71") (name "Net-(D69-PadC)") (class "Default")
      (node (ref "D69") (pin "C") (pinfunction "C_C") (pintype "passive"))
      (node (ref "D70") (pin "A") (pinfunction "A_A") (pintype "passive"))
    )
    (net (code "72") (name "Net-(D70-PadC)") (class "Default")
      (node (ref "D70") (pin "C") (pinfunction "C_C") (pintype "passive"))
      (node (ref "D71") (pin "A") (pinfunction "A_A") (pintype "passive"))
    )
    (net (code "73") (name "Net-(D71-PadC)") (class "Default")
      (node (ref "D71") (pin "C") (pinfunction "C_C") (pintype "passive"))
      (node (ref "D72") (pin "A") (pinfunction "A_A") (pintype "passive"))
    )
    (net (code "74") (name "Net-(D72-PadC)") (class "Default")
      (node (ref "D72") (pin "C") (pinfunction "C_C") (pintype "passive"))
      (node (ref "R12") (pin "2") (pinfunction "2_2") (pintype "passive"))
    )
  )
)
